# Headphone.net
KiCad netlist of a schematic drawn in Altium Designer
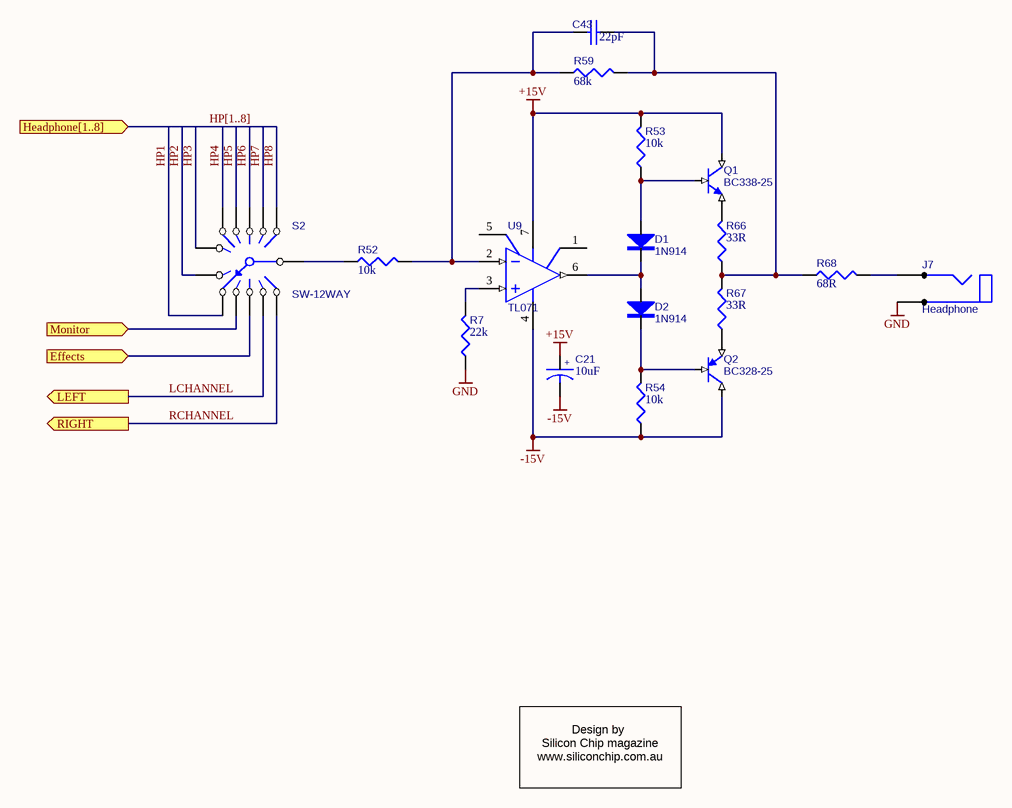
[diagram p0: Headphone.SchDoc]

(export (version "E")
  (design (tool "Eeschema 10.0.6"))
  (components
    (comp (ref "C21")
      (value "10uF")
      (footprint "RB.2/.4")
      (description "Bi-Polar Capacitor")
      (libsource (lib "*") (part "CAPACITOR POL"))
    )
    (comp (ref "C43")
      (value "22pF")
      (footprint "RAD0.2")
      (description "Capacitor")
      (libsource (lib "*") (part "CAP"))
    )
    (comp (ref "D1")
      (value "1N914")
      (footprint "DIODE0.4")
      (description "Diode")
      (libsource (lib "*") (part "1N914"))
    )
    (comp (ref "D2")
      (value "1N914")
      (footprint "DIODE0.4")
      (description "Diode")
      (libsource (lib "*") (part "1N914"))
    )
    (comp (ref "J7")
      (value "Headphone")
      (footprint "JACK-6.25MM")
      (libsource (lib "*") (part "PHONEJACK MONO"))
    )
    (comp (ref "Q1")
      (value "BC338-25")
      (footprint "TO-92A")
      (description "NPN BJT")
      (libsource (lib "*") (part "BC338-25"))
    )
    (comp (ref "Q2")
      (value "BC328-25")
      (footprint "TO-92A")
      (description "PNP BJT")
      (libsource (lib "*") (part "BC328-25"))
    )
    (comp (ref "R7")
      (value "22k")
      (footprint "AXIAL0.4")
      (description "Resistor")
      (libsource (lib "*") (part "RES1"))
    )
    (comp (ref "R52")
      (value "10k")
      (footprint "AXIAL0.4")
      (description "Resistor")
      (libsource (lib "") (part "RES1_1"))
    )
    (comp (ref "R53")
      (value "10k")
      (footprint "AXIAL0.4")
      (description "Resistor")
      (libsource (lib "*") (part "RES1"))
    )
    (comp (ref "R54")
      (value "10k")
      (footprint "AXIAL0.4")
      (description "Resistor")
      (libsource (lib "*") (part "RES1"))
    )
    (comp (ref "R59")
      (value "68k")
      (footprint "AXIAL0.4")
      (description "Resistor")
      (libsource (lib "") (part "RES1_1"))
    )
    (comp (ref "R66")
      (value "33R")
      (footprint "AXIAL0.4")
      (description "Resistor")
      (libsource (lib "*") (part "RES1"))
    )
    (comp (ref "R67")
      (value "33R")
      (footprint "AXIAL0.4")
      (description "Resistor")
      (libsource (lib "*") (part "RES1"))
    )
    (comp (ref "R68")
      (value "68R")
      (footprint "AXIAL0.4")
      (description "Resistor")
      (libsource (lib "") (part "RES1_1"))
    )
    (comp (ref "S2") (value "SW-12WAY") (footprint "SW-12WAY") (libsource (lib "*") (part "SW-12WAY")))
    (comp (ref "U9")
      (value "TL071")
      (footprint "DIP8")
      (description "Low-Noise  JFET-Input Operational Amplifiers")
      (libsource (lib "*") (part "TL071"))
    )
  )
  (nets
    (net (code "1") (name "+15V") (class "Default")
      (node (ref "C21") (pin "1") (pinfunction "1_1") (pintype "passive"))
      (node (ref "Q1") (pin "1") (pinfunction "C_1") (pintype "input"))
      (node (ref "R53") (pin "2") (pinfunction "2_2") (pintype "passive"))
      (node (ref "U9") (pin "7") (pinfunction "VCC+_7") (pintype "power_in"))
    )
    (net (code "2") (name "-15V") (class "Default")
      (node (ref "C21") (pin "2") (pinfunction "2_2") (pintype "passive"))
      (node (ref "Q2") (pin "1") (pinfunction "C_1") (pintype "input"))
      (node (ref "R54") (pin "1") (pinfunction "1_1") (pintype "passive"))
      (node (ref "U9") (pin "4") (pinfunction "VCC-_4") (pintype "power_in"))
    )
    (net (code "3") (name "/Effects") (class "Default")
      (node (ref "S2") (pin "10") (pinfunction "10_10") (pintype "passive"))
    )
    (net (code "4") (name "/HP1") (class "Default")
      (node (ref "S2") (pin "8") (pinfunction "8_8") (pintype "passive"))
    )
    (net (code "5") (name "/HP2") (class "Default")
      (node (ref "S2") (pin "7") (pinfunction "7_7") (pintype "passive"))
    )
    (net (code "6") (name "/HP3") (class "Default")
      (node (ref "S2") (pin "6") (pinfunction "6_6") (pintype "passive"))
    )
    (net (code "7") (name "/HP4") (class "Default")
      (node (ref "S2") (pin "5") (pinfunction "5_5") (pintype "passive"))
    )
    (net (code "8") (name "/HP5") (class "Default")
      (node (ref "S2") (pin "4") (pinfunction "4_4") (pintype "passive"))
    )
    (net (code "9") (name "/HP6") (class "Default")
      (node (ref "S2") (pin "3") (pinfunction "3_3") (pintype "passive"))
    )
    (net (code "10") (name "/HP7") (class "Default")
      (node (ref "S2") (pin "2") (pinfunction "2_2") (pintype "passive"))
    )
    (net (code "11") (name "/HP8") (class "Default")
      (node (ref "S2") (pin "1") (pinfunction "1_1") (pintype "passive"))
    )
    (net (code "13") (name "/LCHANNEL") (class "Default")
      (node (ref "S2") (pin "11") (pinfunction "11_11") (pintype "passive"))
    )
    (net (code "14") (name "/Monitor") (class "Default")
      (node (ref "S2") (pin "9") (pinfunction "9_9") (pintype "passive"))
    )
    (net (code "15") (name "/RCHANNEL") (class "Default")
      (node (ref "S2") (pin "12") (pinfunction "12_12") (pintype "passive"))
    )
    (net (code "16") (name "GND") (class "Default")
      (node (ref "J7") (pin "3") (pinfunction "C_3") (pintype "passive"))
      (node (ref "R7") (pin "1") (pinfunction "1_1") (pintype "passive"))
    )
    (net (code "17") (name "Net-(C43-Pad2)") (class "Default")
      (node (ref "C43") (pin "2") (pinfunction "2_2") (pintype "passive"))
      (node (ref "R59") (pin "2") (pinfunction "2_2") (pintype "passive"))
      (node (ref "R66") (pin "1") (pinfunction "1_1") (pintype "passive"))
      (node (ref "R67") (pin "2") (pinfunction "2_2") (pintype "passive"))
      (node (ref "R68") (pin "1") (pinfunction "1_1") (pintype "passive"))
    )
    (net (code "18") (name "Net-(D1-A)") (class "Default")
      (node (ref "D1") (pin "1") (pinfunction "A_1") (pintype "passive"))
      (node (ref "Q1") (pin "2") (pinfunction "B_2") (pintype "input"))
      (node (ref "R53") (pin "1") (pinfunction "1_1") (pintype "passive"))
    )
    (net (code "19") (name "Net-(D1-K)") (class "Default")
      (node (ref "D1") (pin "2") (pinfunction "K_2") (pintype "passive"))
      (node (ref "D2") (pin "1") (pinfunction "A_1") (pintype "passive"))
      (node (ref "U9") (pin "6") (pinfunction "OUT_6") (pintype "output"))
    )
    (net (code "20") (name "Net-(D2-K)") (class "Default")
      (node (ref "D2") (pin "2") (pinfunction "K_2") (pintype "passive"))
      (node (ref "Q2") (pin "2") (pinfunction "B_2") (pintype "input"))
      (node (ref "R54") (pin "2") (pinfunction "2_2") (pintype "passive"))
    )
    (net (code "21") (name "Net-(J7-A)") (class "Default")
      (node (ref "J7") (pin "1") (pinfunction "A_1") (pintype "passive"))
      (node (ref "R68") (pin "2") (pinfunction "2_2") (pintype "passive"))
    )
    (net (code "22") (name "Net-(Q1-E)") (class "Default")
      (node (ref "Q1") (pin "3") (pinfunction "E_3") (pintype "input"))
      (node (ref "R66") (pin "2") (pinfunction "2_2") (pintype "passive"))
    )
    (net (code "23") (name "Net-(Q2-E)") (class "Default")
      (node (ref "Q2") (pin "3") (pinfunction "E_3") (pintype "input"))
      (node (ref "R67") (pin "1") (pinfunction "1_1") (pintype "passive"))
    )
    (net (code "24") (name "Net-(R52-Pad1)") (class "Default")
      (node (ref "R52") (pin "1") (pinfunction "1_1") (pintype "passive"))
      (node (ref "S2") (pin "13") (pinfunction "13_13") (pintype "passive"))
    )
    (net (code "25") (name "Net-(U9-IN+)") (class "Default")
      (node (ref "R7") (pin "2") (pinfunction "2_2") (pintype "passive"))
      (node (ref "U9") (pin "3") (pinfunction "IN+_3") (pintype "input"))
    )
    (net (code "26") (name "Net-(U9-IN-)") (class "Default")
      (node (ref "C43") (pin "1") (pinfunction "1_1") (pintype "passive"))
      (node (ref "R52") (pin "2") (pinfunction "2_2") (pintype "passive"))
      (node (ref "R59") (pin "1") (pinfunction "1_1") (pintype "passive"))
      (node (ref "U9") (pin "2") (pinfunction "IN-_2") (pintype "input"))
    )
    (net (code "27") (name "unconnected-(U9-N1{slash}O.S.-Pad1)") (class "Default")
      (node (ref "U9") (pin "1") (pinfunction "N1/O.S._1") (pintype "passive"))
    )
    (net (code "28") (name "unconnected-(U9-O.S._N2-Pad5)") (class "Default")
      (node (ref "U9") (pin "5") (pinfunction "O.S._N2_5") (pintype "passive"))
    )
  )
)
